# D5035-01.net
KiCad netlist of a schematic drawn in Altium Designer
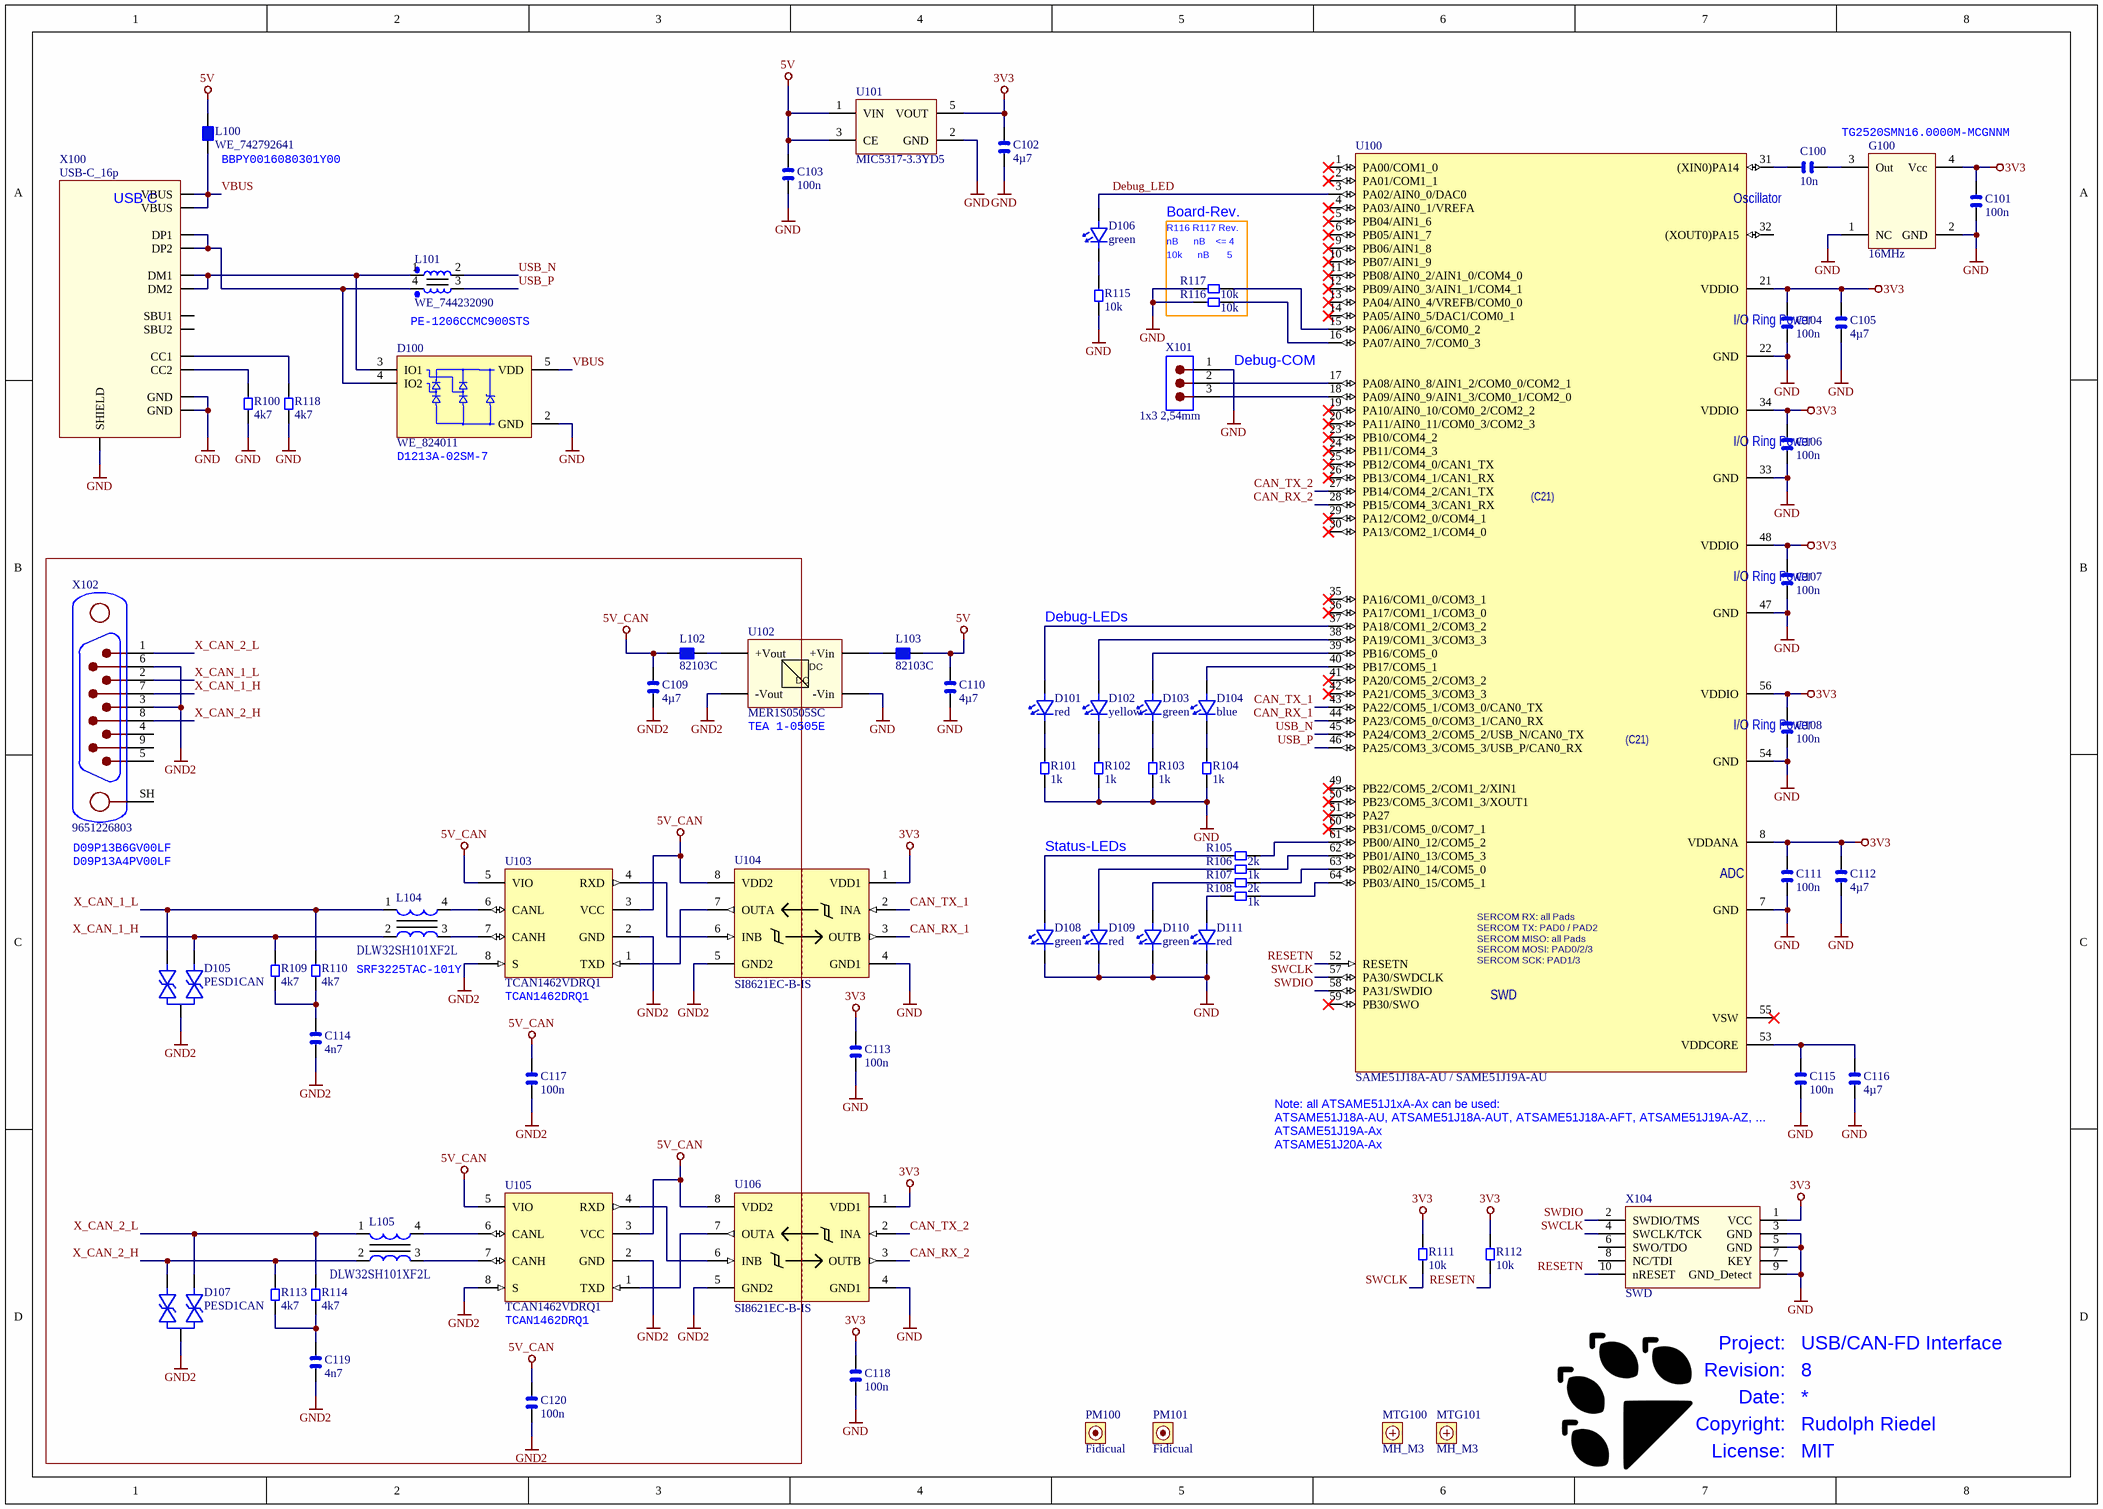
[diagram p0: D5035-01.SchDoc]

(export (version "E")
  (design (tool "Eeschema 10.0.6"))
  (components
    (comp (ref "C100")
      (value "10n")
      (footprint "CAPC1608X09L")
      (description "0603 Chip Capacitor")
      (fields (field (name "PART NUMBER") "CAPC_0603") (field (name "EDITOR") "rriedel"))
      (libsource (lib "HW-Labor_GF") (part "CAP_2_V2"))
    )
    (comp (ref "C101")
      (value "100n")
      (footprint "CAPC1608X09L")
      (description "0603 Chip Capacitor")
      (fields (field (name "PART NUMBER") "CAPC_0603") (field (name "EDITOR") "rriedel"))
      (libsource (lib "HW-Labor_GF") (part "CAP_2_V2"))
    )
    (comp (ref "C102")
      (value "4µ7")
      (footprint "CAPC2012X14L")
      (description "0805 Chip Capacitor")
      (fields (field (name "PART NUMBER") "CAPC_0805") (field (name "EDITOR") "rriedel"))
      (libsource (lib "HW-Labor_GF") (part "CAP_2_V2"))
    )
    (comp (ref "C103")
      (value "100n")
      (footprint "CAPC1608X09L")
      (description "0603 Chip Capacitor")
      (fields (field (name "PART NUMBER") "CAPC_0603") (field (name "EDITOR") "rriedel"))
      (libsource (lib "HW-Labor_GF") (part "CAP_2_V2"))
    )
    (comp (ref "C104")
      (value "100n")
      (footprint "CAPC1608X09L")
      (description "0603 Chip Capacitor")
      (fields (field (name "PART NUMBER") "CAPC_0603") (field (name "EDITOR") "rriedel"))
      (libsource (lib "HW-Labor_GF") (part "CAP_2_V2"))
    )
    (comp (ref "C105")
      (value "4µ7")
      (footprint "CAPC2012X14L")
      (description "0805 Chip Capacitor")
      (fields (field (name "PART NUMBER") "CAPC_0805") (field (name "EDITOR") "rriedel"))
      (libsource (lib "HW-Labor_GF") (part "CAP_2_V2"))
    )
    (comp (ref "C106")
      (value "100n")
      (footprint "CAPC1608X09L")
      (description "0603 Chip Capacitor")
      (fields (field (name "PART NUMBER") "CAPC_0603") (field (name "EDITOR") "rriedel"))
      (libsource (lib "HW-Labor_GF") (part "CAP_2_V2"))
    )
    (comp (ref "C107")
      (value "100n")
      (footprint "CAPC1608X09L")
      (description "0603 Chip Capacitor")
      (fields (field (name "PART NUMBER") "CAPC_0603") (field (name "EDITOR") "rriedel"))
      (libsource (lib "HW-Labor_GF") (part "CAP_2_V2"))
    )
    (comp (ref "C108")
      (value "100n")
      (footprint "CAPC1608X09L")
      (description "0603 Chip Capacitor")
      (fields (field (name "PART NUMBER") "CAPC_0603") (field (name "EDITOR") "rriedel"))
      (libsource (lib "HW-Labor_GF") (part "CAP_2_V2"))
    )
    (comp (ref "C109")
      (value "4µ7")
      (footprint "CAPC2012X14L")
      (description "0805 Chip Capacitor")
      (fields (field (name "PART NUMBER") "CAPC_0805") (field (name "EDITOR") "rriedel"))
      (libsource (lib "HW-Labor_GF") (part "CAP_2_V2"))
    )
    (comp (ref "C110")
      (value "4µ7")
      (footprint "CAPC2012X14L")
      (description "0805 Chip Capacitor")
      (fields (field (name "PART NUMBER") "CAPC_0805") (field (name "EDITOR") "rriedel"))
      (libsource (lib "HW-Labor_GF") (part "CAP_2_V2"))
    )
    (comp (ref "C111")
      (value "100n")
      (footprint "CAPC1608X09L")
      (description "0603 Chip Capacitor")
      (fields (field (name "PART NUMBER") "CAPC_0603") (field (name "EDITOR") "rriedel"))
      (libsource (lib "HW-Labor_GF") (part "CAP_2_V2"))
    )
    (comp (ref "C112")
      (value "4µ7")
      (footprint "CAPC2012X14L")
      (description "0805 Chip Capacitor")
      (fields (field (name "PART NUMBER") "CAPC_0805") (field (name "EDITOR") "rriedel"))
      (libsource (lib "HW-Labor_GF") (part "CAP_2_V2"))
    )
    (comp (ref "C113")
      (value "100n")
      (footprint "CAPC1608X09L")
      (description "0603 Chip Capacitor")
      (fields (field (name "PART NUMBER") "CAPC_0603") (field (name "EDITOR") "rriedel"))
      (libsource (lib "HW-Labor_GF") (part "CAP_2_V2"))
    )
    (comp (ref "C114")
      (value "4n7")
      (footprint "CAPC2012X14L")
      (description "0805 Chip Capacitor")
      (fields (field (name "PART NUMBER") "CAPC_0805") (field (name "EDITOR") "rriedel"))
      (libsource (lib "HW-Labor_GF") (part "CAP_2_V2"))
    )
    (comp (ref "C115")
      (value "100n")
      (footprint "CAPC1608X09L")
      (description "0603 Chip Capacitor")
      (fields (field (name "PART NUMBER") "CAPC_0603") (field (name "EDITOR") "rriedel"))
      (libsource (lib "HW-Labor_GF") (part "CAP_2_V2"))
    )
    (comp (ref "C116")
      (value "4µ7")
      (footprint "CAPC2012X14L")
      (description "0805 Chip Capacitor")
      (fields (field (name "PART NUMBER") "CAPC_0805") (field (name "EDITOR") "rriedel"))
      (libsource (lib "HW-Labor_GF") (part "CAP_2_V2"))
    )
    (comp (ref "C117")
      (value "100n")
      (footprint "CAPC1608X09L")
      (description "0603 Chip Capacitor")
      (fields (field (name "PART NUMBER") "CAPC_0603") (field (name "EDITOR") "rriedel"))
      (libsource (lib "HW-Labor_GF") (part "CAP_2_V2"))
    )
    (comp (ref "C118")
      (value "100n")
      (footprint "CAPC1608X09L")
      (description "0603 Chip Capacitor")
      (fields (field (name "PART NUMBER") "CAPC_0603") (field (name "EDITOR") "rriedel"))
      (libsource (lib "HW-Labor_GF") (part "CAP_2_V2"))
    )
    (comp (ref "C119")
      (value "4n7")
      (footprint "CAPC2012X14L")
      (description "0805 Chip Capacitor")
      (fields (field (name "PART NUMBER") "CAPC_0805") (field (name "EDITOR") "rriedel"))
      (libsource (lib "HW-Labor_GF") (part "CAP_2_V2"))
    )
    (comp (ref "C120")
      (value "100n")
      (footprint "CAPC1608X09L")
      (description "0603 Chip Capacitor")
      (fields (field (name "PART NUMBER") "CAPC_0603") (field (name "EDITOR") "rriedel"))
      (libsource (lib "HW-Labor_GF") (part "CAP_2_V2"))
    )
    (comp (ref "D100")
      (value "WE_824011")
      (footprint "SOT95P280X110-5N")
      (description "TVS Diode Array WE-TVS")
      (fields
        (field (name "MANUFACTURER") "Wuerth")
        (field (name "DISTRIBUTOR_1_PART_NUMBER") "732-4465-1-ND")
        (field (name "EDITOR") "rriedel")
      )
      (libsource (lib "HW-Labor_GF") (part "WE-824011"))
    )
    (comp (ref "D101")
      (value "red")
      (footprint "DIOC1608X06N_LED")
      (description "LED, 0603")
      (fields (field (name "PART NUMBER") "LED_0603") (field (name "EDITOR") "rriedel"))
      (libsource (lib "HW-Labor_GF") (part "LED_generic"))
    )
    (comp (ref "D102")
      (value "yellow")
      (footprint "DIOC1608X06N_LED")
      (description "LED, 0603")
      (fields (field (name "PART NUMBER") "LED_0603") (field (name "EDITOR") "rriedel"))
      (libsource (lib "HW-Labor_GF") (part "LED_generic"))
    )
    (comp (ref "D103")
      (value "green")
      (footprint "DIOC1608X06N_LED")
      (description "LED, 0603")
      (fields (field (name "PART NUMBER") "LED_0603") (field (name "EDITOR") "rriedel"))
      (libsource (lib "HW-Labor_GF") (part "LED_generic"))
    )
    (comp (ref "D104")
      (value "blue")
      (footprint "DIOC1608X06N_LED")
      (description "LED, 0603")
      (fields (field (name "PART NUMBER") "LED_0603") (field (name "EDITOR") "rriedel"))
      (libsource (lib "HW-Labor_GF") (part "LED_generic"))
    )
    (comp (ref "D105")
      (value "PESD1CAN")
      (footprint "SOT95P280X110-3N")
      (description "CAN bus ESD protection diode")
      (fields
        (field (name "MANUFACTURER") "Nexperia")
        (field (name "DISTRIBUTOR_1_PART_NUMBER") "1727-3817-1-ND")
        (field (name "EDITOR") "rriedel")
      )
      (libsource (lib "HW-Labor_GF") (part "PESD1CAN"))
    )
    (comp (ref "D106")
      (value "green")
      (footprint "DIOC1608X06N_LED")
      (description "LED, 0603")
      (fields (field (name "PART NUMBER") "LED_0603") (field (name "EDITOR") "rriedel"))
      (libsource (lib "HW-Labor_GF") (part "LED_generic"))
    )
    (comp (ref "D107")
      (value "PESD1CAN")
      (footprint "SOT95P280X110-3N")
      (description "CAN bus ESD protection diode")
      (fields
        (field (name "MANUFACTURER") "Nexperia")
        (field (name "DISTRIBUTOR_1_PART_NUMBER") "1727-3817-1-ND")
        (field (name "EDITOR") "rriedel")
      )
      (libsource (lib "HW-Labor_GF") (part "PESD1CAN"))
    )
    (comp (ref "D108")
      (value "green")
      (footprint "DIOC1608X06N_LED")
      (description "LED, 0603")
      (fields (field (name "PART NUMBER") "LED_0603") (field (name "EDITOR") "rriedel"))
      (libsource (lib "HW-Labor_GF") (part "LED_generic"))
    )
    (comp (ref "D109")
      (value "red")
      (footprint "DIOC1608X06N_LED")
      (description "LED, 0603")
      (fields (field (name "PART NUMBER") "LED_0603") (field (name "EDITOR") "rriedel"))
      (libsource (lib "HW-Labor_GF") (part "LED_generic"))
    )
    (comp (ref "D110")
      (value "green")
      (footprint "DIOC1608X06N_LED")
      (description "LED, 0603")
      (fields (field (name "PART NUMBER") "LED_0603") (field (name "EDITOR") "rriedel"))
      (libsource (lib "HW-Labor_GF") (part "LED_generic"))
    )
    (comp (ref "D111")
      (value "red")
      (footprint "DIOC1608X06N_LED")
      (description "LED, 0603")
      (fields (field (name "PART NUMBER") "LED_0603") (field (name "EDITOR") "rriedel"))
      (libsource (lib "HW-Labor_GF") (part "LED_generic"))
    )
    (comp (ref "G100")
      (value "16MHz")
      (footprint "TG2520")
      (description "16MHz Oscillator, +/- 0.5ppm")
      (fields
        (field (name "PART NUMBER") "TG2520SMN16.0000M-MCGNNM")
        (field (name "MANUFACTURER") "Epson")
        (field (name "EDITOR") "rriedel")
      )
      (libsource (lib "HW-Labor_GF") (part "TG2520"))
    )
    (comp (ref "L100")
      (value "WE_742792641")
      (footprint "INDC1608X06L")
      (description "SMT EMI suppression ferrite bead WE-CBF")
      (fields
        (field (name "MANUFACTURER") "Wuerth")
        (field (name "DISTRIBUTOR_1_PART_NUMBER") "732-1592-1-ND")
        (field (name "EDITOR") "rriedel")
      )
      (libsource (lib "HW-Labor_GF") (part "IND_2_V1"))
    )
    (comp (ref "L101")
      (value "WE_744232090")
      (footprint "WE_744232090")
      (description "SMD common mode noise suppressor WE-CNSW")
      (fields
        (field (name "MANUFACTURER") "Wuerth")
        (field (name "DISTRIBUTOR_1_PART_NUMBER") "732-1469-1-ND")
        (field (name "EDITOR") "rriedel")
      )
      (libsource (lib "HW-Labor_GF") (part "WE_744232090"))
    )
    (comp (ref "L102")
      (value "82103C")
      (footprint "Murata_8200C")
      (description "10µH, 0,5A, 400mR")
      (fields
        (field (name "MANUFACTURER") "Murata")
        (field (name "DISTRIBUTOR_1_PART_NUMBER") "811-2473-1-ND")
        (field (name "EDITOR") "rriedel")
      )
      (libsource (lib "HW-Labor_GF") (part "IND_2_V1"))
    )
    (comp (ref "L103")
      (value "82103C")
      (footprint "Murata_8200C")
      (description "10µH, 0,5A, 400mR")
      (fields
        (field (name "MANUFACTURER") "Murata")
        (field (name "DISTRIBUTOR_1_PART_NUMBER") "811-2473-1-ND")
        (field (name "EDITOR") "rriedel")
      )
      (libsource (lib "HW-Labor_GF") (part "IND_2_V1"))
    )
    (comp (ref "L104")
      (value "DLW32SH101XF2L‎")
      (footprint "ACT1210")
      (description "Common Mode Filter,  -50°C ... +150°C, AEC-Q200")
      (fields
        (field (name "PART NUMBER") "ACT1210-101-2P-TL00")
        (field (name "MANUFACTURER") "TDK")
        (field (name "EDITOR") "rriedel")
      )
      (libsource (lib "HW-Labor_GF") (part "CAN_DROSSEL"))
    )
    (comp (ref "L105")
      (value "DLW32SH101XF2L‎")
      (footprint "ACT1210")
      (description "Common Mode Filter,  -50°C ... +150°C, AEC-Q200")
      (fields
        (field (name "PART NUMBER") "ACT1210-101-2P-TL00")
        (field (name "MANUFACTURER") "TDK")
        (field (name "EDITOR") "rriedel")
      )
      (libsource (lib "HW-Labor_GF") (part "CAN_DROSSEL"))
    )
    (comp (ref "MTG100")
      (value "MH_M3")
      (footprint "HOLE_3_2MM")
      (description "Mounting-Hole for M3 screws")
      (fields (field (name "EDITOR") "rriedel"))
      (libsource (lib "HW-Labor_GF") (part "MTG_V1"))
    )
    (comp (ref "MTG101")
      (value "MH_M3")
      (footprint "HOLE_3_2MM")
      (description "Mounting-Hole for M3 screws")
      (fields (field (name "EDITOR") "rriedel"))
      (libsource (lib "HW-Labor_GF") (part "MTG_V1"))
    )
    (comp (ref "PM100")
      (value "Fidicual")
      (footprint "PM100")
      (fields (field (name "PART NUMBER") "PM100") (field (name "EDITOR") "rriedel"))
      (libsource (lib "HW-Labor_GF") (part "PM100"))
    )
    (comp (ref "PM101")
      (value "Fidicual")
      (footprint "PM100")
      (fields (field (name "PART NUMBER") "PM100") (field (name "EDITOR") "rriedel"))
      (libsource (lib "HW-Labor_GF") (part "PM100"))
    )
    (comp (ref "R100")
      (value "4k7")
      (footprint "RESC2012X06L")
      (description "0805 Chip Resistor")
      (fields (field (name "PART NUMBER") "RESC_0805") (field (name "EDITOR") "rriedel"))
      (libsource (lib "HW-Labor_GF") (part "RES_2_V2"))
    )
    (comp (ref "R101")
      (value "1k")
      (footprint "RESC1608X06L")
      (description "0603 Chip Resistor")
      (fields (field (name "PART NUMBER") "RESC_0603") (field (name "EDITOR") "rriedel"))
      (libsource (lib "HW-Labor_GF") (part "RES_2_V2"))
    )
    (comp (ref "R102")
      (value "1k")
      (footprint "RESC1608X06L")
      (description "0603 Chip Resistor")
      (fields (field (name "PART NUMBER") "RESC_0603") (field (name "EDITOR") "rriedel"))
      (libsource (lib "HW-Labor_GF") (part "RES_2_V2"))
    )
    (comp (ref "R103")
      (value "1k")
      (footprint "RESC1608X06L")
      (description "0603 Chip Resistor")
      (fields (field (name "PART NUMBER") "RESC_0603") (field (name "EDITOR") "rriedel"))
      (libsource (lib "HW-Labor_GF") (part "RES_2_V2"))
    )
    (comp (ref "R104")
      (value "1k")
      (footprint "RESC1608X06L")
      (description "0603 Chip Resistor")
      (fields (field (name "PART NUMBER") "RESC_0603") (field (name "EDITOR") "rriedel"))
      (libsource (lib "HW-Labor_GF") (part "RES_2_V2"))
    )
    (comp (ref "R105")
      (value "2k")
      (footprint "RESC1608X06L")
      (description "0603 Chip Resistor")
      (fields (field (name "PART NUMBER") "RESC_0603") (field (name "EDITOR") "rriedel"))
      (libsource (lib "HW-Labor_GF") (part "RES_2_V2"))
    )
    (comp (ref "R106")
      (value "1k")
      (footprint "RESC1608X06L")
      (description "0603 Chip Resistor")
      (fields (field (name "PART NUMBER") "RESC_0603") (field (name "EDITOR") "rriedel"))
      (libsource (lib "HW-Labor_GF") (part "RES_2_V2"))
    )
    (comp (ref "R107")
      (value "2k")
      (footprint "RESC1608X06L")
      (description "0603 Chip Resistor")
      (fields (field (name "PART NUMBER") "RESC_0603") (field (name "EDITOR") "rriedel"))
      (libsource (lib "HW-Labor_GF") (part "RES_2_V2"))
    )
    (comp (ref "R108")
      (value "1k")
      (footprint "RESC1608X06L")
      (description "0603 Chip Resistor")
      (fields (field (name "PART NUMBER") "RESC_0603") (field (name "EDITOR") "rriedel"))
      (libsource (lib "HW-Labor_GF") (part "RES_2_V2"))
    )
    (comp (ref "R109")
      (value "4k7")
      (footprint "RESC2012X06L")
      (description "0805 Chip Resistor")
      (fields (field (name "PART NUMBER") "RESC_0805") (field (name "EDITOR") "rriedel"))
      (libsource (lib "HW-Labor_GF") (part "RES_2_V2"))
    )
    (comp (ref "R110")
      (value "4k7")
      (footprint "RESC2012X06L")
      (description "0805 Chip Resistor")
      (fields (field (name "PART NUMBER") "RESC_0805") (field (name "EDITOR") "rriedel"))
      (libsource (lib "HW-Labor_GF") (part "RES_2_V2"))
    )
    (comp (ref "R111")
      (value "10k")
      (footprint "RESC1608X06L")
      (description "0603 Chip Resistor")
      (fields (field (name "PART NUMBER") "RESC_0603") (field (name "EDITOR") "rriedel"))
      (libsource (lib "HW-Labor_GF") (part "RES_2_V2"))
    )
    (comp (ref "R112")
      (value "10k")
      (footprint "RESC1608X06L")
      (description "0603 Chip Resistor")
      (fields (field (name "PART NUMBER") "RESC_0603") (field (name "EDITOR") "rriedel"))
      (libsource (lib "HW-Labor_GF") (part "RES_2_V2"))
    )
    (comp (ref "R113")
      (value "4k7")
      (footprint "RESC2012X06L")
      (description "0805 Chip Resistor")
      (fields (field (name "PART NUMBER") "RESC_0805") (field (name "EDITOR") "rriedel"))
      (libsource (lib "HW-Labor_GF") (part "RES_2_V2"))
    )
    (comp (ref "R114")
      (value "4k7")
      (footprint "RESC2012X06L")
      (description "0805 Chip Resistor")
      (fields (field (name "PART NUMBER") "RESC_0805") (field (name "EDITOR") "rriedel"))
      (libsource (lib "HW-Labor_GF") (part "RES_2_V2"))
    )
    (comp (ref "R115")
      (value "10k")
      (footprint "RESC1608X06L")
      (description "0603 Chip Resistor")
      (fields (field (name "PART NUMBER") "RESC_0603") (field (name "EDITOR") "rriedel"))
      (libsource (lib "HW-Labor_GF") (part "RES_2_V2"))
    )
    (comp (ref "R116")
      (value "10k")
      (footprint "RESC1608X06L")
      (description "0603 Chip Resistor")
      (fields (field (name "PART NUMBER") "RESC_0603") (field (name "EDITOR") "rriedel"))
      (libsource (lib "HW-Labor_GF") (part "RES_2_V2"))
    )
    (comp (ref "R117")
      (value "10k")
      (footprint "RESC1608X06L")
      (description "0603 Chip Resistor")
      (fields (field (name "PART NUMBER") "RESC_0603") (field (name "EDITOR") "rriedel"))
      (libsource (lib "HW-Labor_GF") (part "RES_2_V2"))
    )
    (comp (ref "R118")
      (value "4k7")
      (footprint "RESC2012X06L")
      (description "0805 Chip Resistor")
      (fields (field (name "PART NUMBER") "RESC_0805") (field (name "EDITOR") "rriedel"))
      (libsource (lib "HW-Labor_GF") (part "RES_2_V2"))
    )
    (comp (ref "U100")
      (value "SAME51J18A-AU / SAME51J19A-AU")
      (footprint "TSQFP50P1200X1200X120-64N")
      (description "32-bit Microcontroller, 120MHz Cortex M4-F, 512k FLASH,  2x CAN-FD, -40…85°C")
      (fields
        (field (name "PART NUMBER") "SAME51J19A-AU")
        (field (name "MANUFACTURER") "Microchip")
        (field (name "EDITOR") "rriedel")
      )
      (libsource (lib "HW-Labor_GF") (part "SAME5xJxxA-AUx"))
    )
    (comp (ref "U101")
      (value "MIC5317-3.3YD5")
      (footprint "SOT95P280X110-5N")
      (description "100 mA LDO,  Vout= 3,3V, -40°C..125°C")
      (fields
        (field (name "PART NUMBER") "MIC5233-3.3")
        (field (name "MANUFACTURER") "Microchip")
        (field (name "EDITOR") "rriedel")
      )
      (libsource (lib "HW-Labor_GF") (part "LDO_SOT23-5"))
    )
    (comp (ref "U102")
      (value "MER1S0505SC")
      (footprint "MER1SxxxxC")
      (description "Isolated 1W Single Output DC-DC Converters 5V/5V 200mA")
      (fields
        (field (name "MANUFACTURER") "Murata")
        (field (name "DISTRIBUTOR_1_PART_NUMBER") "811-2124-5-ND‎")
        (field (name "EDITOR") "rriedel")
      )
      (libsource (lib "HW-Labor_GF") (part "MER1SxxxxC"))
    )
    (comp (ref "U103")
      (value "TCAN1462VDRQ1")
      (footprint "SOIC127P600X175-8N")
      (description "CAN-FD SIC transceiver 8MBit, VIO Pin")
      (fields
        (field (name "MANUFACTURER") "TI")
        (field (name "DISTRIBUTOR_1_PART_NUMBER") "595-TCAN1462VDRQ1")
        (field (name "EDITOR") "rriedel")
      )
      (libsource (lib "HW-Labor_GF") (part "TJA1051T_3"))
    )
    (comp (ref "U104")
      (value "SI8621EC-B-IS")
      (footprint "SOIC127P600X175-8N")
      (description "Dual channel digital isolator, 150Mbit, 3,75kV")
      (fields
        (field (name "MANUFACTURER") "Silicon Labs")
        (field (name "DISTRIBUTOR_1_PART_NUMBER") "336-4776-1-ND")
        (field (name "EDITOR") "rriedel")
      )
      (libsource (lib "HW-Labor_GF") (part "SI8621"))
    )
    (comp (ref "U105")
      (value "TCAN1462VDRQ1")
      (footprint "SOIC127P600X175-8N")
      (description "CAN-FD SIC transceiver 8MBit, VIO Pin")
      (fields
        (field (name "MANUFACTURER") "TI")
        (field (name "DISTRIBUTOR_1_PART_NUMBER") "595-TCAN1462VDRQ1")
        (field (name "EDITOR") "rriedel")
      )
      (libsource (lib "HW-Labor_GF") (part "TJA1051T_3"))
    )
    (comp (ref "U106")
      (value "SI8621EC-B-IS")
      (footprint "SOIC127P600X175-8N")
      (description "Dual channel digital isolator, 150Mbit, 3,75kV")
      (fields
        (field (name "MANUFACTURER") "Silicon Labs")
        (field (name "DISTRIBUTOR_1_PART_NUMBER") "336-4776-1-ND")
        (field (name "EDITOR") "rriedel")
      )
      (libsource (lib "HW-Labor_GF") (part "SI8621"))
    )
    (comp (ref "X100")
      (value "USB-C_16p")
      (footprint "USBC_16P")
      (description "SMD USB-C 16p")
      (fields (field (name "DISTRIBUTOR_1_PART_NUMBER") "C2765186") (field (name "EDITOR") "rriedel"))
      (libsource (lib "HW-Labor_GF") (part "USB-C"))
    )
    (comp (ref "X101")
      (value "1x3 2,54mm")
      (footprint "PINH_1x03_2_54mm")
      (description "Pin-Header 2,54 mm 3pins")
      (fields (field (name "PART NUMBER") "PINH_1x3_2_54") (field (name "EDITOR") "rriedel"))
      (libsource (lib "HW-Labor_GF") (part "CONM_1x3_V2"))
    )
    (comp (ref "X102")
      (value "9651226803")
      (footprint "09651226803")
      (description "D-Sub, 9 pin, male, right angle")
      (fields
        (field (name "PART NUMBER") "09651226803")
        (field (name "MANUFACTURER") "Harting")
        (field (name "EDITOR") "rriedel")
      )
      (libsource (lib "HW-Labor_GF") (part "D_Sub_9_Male"))
    )
    (comp (ref "X104")
      (value "SWD")
      (footprint "FTSH-105-01-L-DV-K")
      (description "ARM Debug-Header 2x5 1,27 mm")
      (fields (field (name "EDITOR") "rriedel"))
      (libsource (lib "HW-Labor_GF") (part "SWD"))
    )
  )
  (nets
    (net (code "1") (name "/CAN_RX_1") (class "Default")
      (node (ref "U100") (pin "44") (pinfunction "PA23/COM5_0/COM3_1/CAN0_RX_44") (pintype "bidirectional"))
      (node (ref "U104") (pin "3") (pinfunction "OUTB_3") (pintype "output"))
    )
    (net (code "2") (name "/CAN_RX_2") (class "Default")
      (node (ref "U100") (pin "28") (pinfunction "PB15/COM4_3/CAN1_RX_28") (pintype "bidirectional"))
      (node (ref "U106") (pin "3") (pinfunction "OUTB_3") (pintype "output"))
    )
    (net (code "3") (name "/CAN_TX_1") (class "Default")
      (node (ref "U100") (pin "43") (pinfunction "PA22/COM5_1/COM3_0/CAN0_TX_43") (pintype "bidirectional"))
      (node (ref "U104") (pin "2") (pinfunction "INA_2") (pintype "input"))
    )
    (net (code "4") (name "/CAN_TX_2") (class "Default")
      (node (ref "U100") (pin "27") (pinfunction "PB14/COM4_2/CAN1_TX_27") (pintype "bidirectional"))
      (node (ref "U106") (pin "2") (pinfunction "INA_2") (pintype "input"))
    )
    (net (code "5") (name "/Debug_LED") (class "Default")
      (node (ref "D106") (pin "2") (pinfunction "2_2") (pintype "passive"))
      (node (ref "U100") (pin "3") (pinfunction "PA02/AIN0_0/DAC0_3") (pintype "bidirectional"))
    )
    (net (code "6") (name "/RESETN") (class "Default")
      (node (ref "R112") (pin "1") (pinfunction "1_1") (pintype "passive"))
      (node (ref "U100") (pin "52") (pinfunction "RESETN_52") (pintype "input"))
      (node (ref "X104") (pin "10") (pinfunction "nRESET_10") (pintype "passive"))
    )
    (net (code "7") (name "/SWCLK") (class "Default")
      (node (ref "R111") (pin "1") (pinfunction "1_1") (pintype "passive"))
      (node (ref "U100") (pin "57") (pinfunction "PA30/SWDCLK_57") (pintype "bidirectional"))
      (node (ref "X104") (pin "4") (pinfunction "SWCLK/TCK_4") (pintype "passive"))
    )
    (net (code "8") (name "/SWDIO") (class "Default")
      (node (ref "U100") (pin "58") (pinfunction "PA31/SWDIO_58") (pintype "bidirectional"))
      (node (ref "X104") (pin "2") (pinfunction "SWDIO/TMS_2") (pintype "passive"))
    )
    (net (code "9") (name "/USB_N") (class "Default")
      (node (ref "L101") (pin "2") (pinfunction "2_2") (pintype "passive"))
      (node (ref "U100") (pin "45") (pinfunction "PA24/COM3_2/COM5_2/USB_N/CAN0_TX_45") (pintype "bidirectional"))
    )
    (net (code "10") (name "/USB_P") (class "Default")
      (node (ref "L101") (pin "3") (pinfunction "3_3") (pintype "passive"))
      (node (ref "U100") (pin "46") (pinfunction "PA25/COM3_3/COM5_3/USB_P/CAN0_RX_46") (pintype "bidirectional"))
    )
    (net (code "11") (name "/VBUS") (class "Default")
      (node (ref "D100") (pin "5") (pinfunction "VDD_5") (pintype "passive"))
      (node (ref "L100") (pin "1") (pinfunction "1_1") (pintype "passive"))
      (node (ref "X100") (pin "A4-B9") (pinfunction "VBUS_A4-B9") (pintype "power_in"))
      (node (ref "X100") (pin "B4-A9") (pinfunction "VBUS_B4-A9") (pintype "power_in"))
    )
    (net (code "12") (name "/X_CAN_1_H") (class "Default")
      (node (ref "D105") (pin "2") (pinfunction "2_2") (pintype "passive"))
      (node (ref "L104") (pin "2") (pintype "passive"))
      (node (ref "R109") (pin "2") (pinfunction "2_2") (pintype "passive"))
      (node (ref "X102") (pin "7") (pinfunction "7_7") (pintype "passive"))
    )
    (net (code "13") (name "/X_CAN_1_L") (class "Default")
      (node (ref "D105") (pin "1") (pinfunction "1_1") (pintype "passive"))
      (node (ref "L104") (pin "1") (pintype "passive"))
      (node (ref "R110") (pin "2") (pinfunction "2_2") (pintype "passive"))
      (node (ref "X102") (pin "2") (pinfunction "2_2") (pintype "passive"))
    )
    (net (code "14") (name "/X_CAN_2_H") (class "Default")
      (node (ref "D107") (pin "1") (pinfunction "1_1") (pintype "passive"))
      (node (ref "L105") (pin "2") (pintype "passive"))
      (node (ref "R113") (pin "2") (pinfunction "2_2") (pintype "passive"))
      (node (ref "X102") (pin "8") (pinfunction "8_8") (pintype "passive"))
    )
    (net (code "15") (name "/X_CAN_2_L") (class "Default")
      (node (ref "D107") (pin "2") (pinfunction "2_2") (pintype "passive"))
      (node (ref "L105") (pin "1") (pintype "passive"))
      (node (ref "R114") (pin "2") (pinfunction "2_2") (pintype "passive"))
      (node (ref "X102") (pin "1") (pinfunction "1_1") (pintype "passive"))
    )
    (net (code "16") (name "3V3") (class "Default")
      (node (ref "C101") (pin "2") (pinfunction "2_2") (pintype "passive"))
      (node (ref "C102") (pin "2") (pinfunction "2_2") (pintype "passive"))
      (node (ref "C104") (pin "2") (pinfunction "2_2") (pintype "passive"))
      (node (ref "C105") (pin "2") (pinfunction "2_2") (pintype "passive"))
      (node (ref "C106") (pin "2") (pinfunction "2_2") (pintype "passive"))
      (node (ref "C107") (pin "2") (pinfunction "2_2") (pintype "passive"))
      (node (ref "C108") (pin "2") (pinfunction "2_2") (pintype "passive"))
      (node (ref "C111") (pin "2") (pinfunction "2_2") (pintype "passive"))
      (node (ref "C112") (pin "2") (pinfunction "2_2") (pintype "passive"))
      (node (ref "C113") (pin "2") (pinfunction "2_2") (pintype "passive"))
      (node (ref "C118") (pin "2") (pinfunction "2_2") (pintype "passive"))
      (node (ref "G100") (pin "4") (pinfunction "Vcc_4") (pintype "passive"))
      (node (ref "R111") (pin "2") (pinfunction "2_2") (pintype "passive"))
      (node (ref "R112") (pin "2") (pinfunction "2_2") (pintype "passive"))
      (node (ref "U100") (pin "21") (pinfunction "VDDIO_21") (pintype "power_in"))
      (node (ref "U100") (pin "34") (pinfunction "VDDIO_34") (pintype "power_in"))
      (node (ref "U100") (pin "48") (pinfunction "VDDIO_48") (pintype "power_in"))
      (node (ref "U100") (pin "56") (pinfunction "VDDIO_56") (pintype "power_in"))
      (node (ref "U100") (pin "8") (pinfunction "VDDANA_8") (pintype "power_in"))
      (node (ref "U101") (pin "5") (pinfunction "VOUT_5") (pintype "passive"))
      (node (ref "U104") (pin "1") (pinfunction "VDD1_1") (pintype "power_in"))
      (node (ref "U106") (pin "1") (pinfunction "VDD1_1") (pintype "power_in"))
      (node (ref "X104") (pin "1") (pinfunction "VCC_1") (pintype "power_in"))
    )
    (net (code "17") (name "5V") (class "Default")
      (node (ref "C103") (pin "2") (pinfunction "2_2") (pintype "passive"))
      (node (ref "C110") (pin "2") (pinfunction "2_2") (pintype "passive"))
      (node (ref "L100") (pin "2") (pinfunction "2_2") (pintype "passive"))
      (node (ref "L103") (pin "1") (pinfunction "1_1") (pintype "passive"))
      (node (ref "U101") (pin "1") (pinfunction "VIN_1") (pintype "passive"))
      (node (ref "U101") (pin "3") (pinfunction "CE_3") (pintype "passive"))
    )
    (net (code "18") (name "5V_CAN") (class "Default")
      (node (ref "C109") (pin "2") (pinfunction "2_2") (pintype "passive"))
      (node (ref "C117") (pin "2") (pinfunction "2_2") (pintype "passive"))
      (node (ref "C120") (pin "2") (pinfunction "2_2") (pintype "passive"))
      (node (ref "L102") (pin "2") (pinfunction "2_2") (pintype "passive"))
      (node (ref "U103") (pin "3") (pinfunction "VCC_3") (pintype "power_in"))
      (node (ref "U103") (pin "5") (pinfunction "VIO_5") (pintype "power_in"))
      (node (ref "U104") (pin "8") (pinfunction "VDD2_8") (pintype "power_in"))
      (node (ref "U105") (pin "3") (pinfunction "VCC_3") (pintype "power_in"))
      (node (ref "U105") (pin "5") (pinfunction "VIO_5") (pintype "power_in"))
      (node (ref "U106") (pin "8") (pinfunction "VDD2_8") (pintype "power_in"))
    )
    (net (code "19") (name "GND") (class "Default")
      (node (ref "C101") (pin "1") (pinfunction "1_1") (pintype "passive"))
      (node (ref "C102") (pin "1") (pinfunction "1_1") (pintype "passive"))
      (node (ref "C103") (pin "1") (pinfunction "1_1") (pintype "passive"))
      (node (ref "C104") (pin "1") (pinfunction "1_1") (pintype "passive"))
      (node (ref "C105") (pin "1") (pinfunction "1_1") (pintype "passive"))
      (node (ref "C106") (pin "1") (pinfunction "1_1") (pintype "passive"))
      (node (ref "C107") (pin "1") (pinfunction "1_1") (pintype "passive"))
      (node (ref "C108") (pin "1") (pinfunction "1_1") (pintype "passive"))
      (node (ref "C110") (pin "1") (pinfunction "1_1") (pintype "passive"))
      (node (ref "C111") (pin "1") (pinfunction "1_1") (pintype "passive"))
      (node (ref "C112") (pin "1") (pinfunction "1_1") (pintype "passive"))
      (node (ref "C113") (pin "1") (pinfunction "1_1") (pintype "passive"))
      (node (ref "C115") (pin "1") (pinfunction "1_1") (pintype "passive"))
      (node (ref "C116") (pin "1") (pinfunction "1_1") (pintype "passive"))
      (node (ref "C118") (pin "1") (pinfunction "1_1") (pintype "passive"))
      (node (ref "D100") (pin "2") (pinfunction "GND_2") (pintype "passive"))
      (node (ref "D108") (pin "1") (pinfunction "1_1") (pintype "passive"))
      (node (ref "D109") (pin "1") (pinfunction "1_1") (pintype "passive"))
      (node (ref "D110") (pin "1") (pinfunction "1_1") (pintype "passive"))
      (node (ref "D111") (pin "1") (pinfunction "1_1") (pintype "passive"))
      (node (ref "G100") (pin "1") (pinfunction "NC_1") (pintype "passive"))
      (node (ref "G100") (pin "2") (pinfunction "GND_2") (pintype "power_in"))
      (node (ref "R100") (pin "1") (pinfunction "1_1") (pintype "passive"))
      (node (ref "R101") (pin "1") (pinfunction "1_1") (pintype "passive"))
      (node (ref "R102") (pin "1") (pinfunction "1_1") (pintype "passive"))
      (node (ref "R103") (pin "1") (pinfunction "1_1") (pintype "passive"))
      (node (ref "R104") (pin "1") (pinfunction "1_1") (pintype "passive"))
      (node (ref "R115") (pin "1") (pinfunction "1_1") (pintype "passive"))
      (node (ref "R116") (pin "2") (pinfunction "2_2") (pintype "passive"))
      (node (ref "R117") (pin "2") (pinfunction "2_2") (pintype "passive"))
      (node (ref "R118") (pin "1") (pinfunction "1_1") (pintype "passive"))
      (node (ref "U100") (pin "22") (pinfunction "GND_22") (pintype "power_in"))
      (node (ref "U100") (pin "33") (pinfunction "GND_33") (pintype "power_in"))
      (node (ref "U100") (pin "47") (pinfunction "GND_47") (pintype "power_in"))
      (node (ref "U100") (pin "54") (pinfunction "GND_54") (pintype "power_in"))
      (node (ref "U100") (pin "7") (pinfunction "GND_7") (pintype "power_in"))
      (node (ref "U101") (pin "2") (pinfunction "GND_2") (pintype "passive"))
      (node (ref "U102") (pin "2") (pinfunction "-Vin_2") (pintype "power_in"))
      (node (ref "U104") (pin "4") (pinfunction "GND1_4") (pintype "power_in"))
      (node (ref "U106") (pin "4") (pinfunction "GND1_4") (pintype "power_in"))
      (node (ref "X100") (pin "A1-B12") (pinfunction "GND_A1-B12") (pintype "power_in"))
      (node (ref "X100") (pin "B1-A12") (pinfunction "GND_B1-A12") (pintype "power_in"))
      (node (ref "X100") (pin "SHIELD") (pinfunction "SHIELD_SHIELD") (pintype "passive"))
      (node (ref "X101") (pin "1") (pinfunction "1_1") (pintype "passive"))
      (node (ref "X104") (pin "3") (pinfunction "GND_3") (pintype "power_in"))
      (node (ref "X104") (pin "5") (pinfunction "GND_5") (pintype "power_in"))
      (node (ref "X104") (pin "9") (pinfunction "GND_Detect_9") (pintype "power_in"))
    )
    (net (code "20") (name "GND2") (class "Default")
      (node (ref "C109") (pin "1") (pinfunction "1_1") (pintype "passive"))
      (node (ref "C114") (pin "1") (pinfunction "1_1") (pintype "passive"))
      (node (ref "C117") (pin "1") (pinfunction "1_1") (pintype "passive"))
      (node (ref "C119") (pin "1") (pinfunction "1_1") (pintype "passive"))
      (node (ref "C120") (pin "1") (pinfunction "1_1") (pintype "passive"))
      (node (ref "D105") (pin "3") (pinfunction "3_3") (pintype "passive"))
      (node (ref "D107") (pin "3") (pinfunction "3_3") (pintype "passive"))
      (node (ref "U102") (pin "4") (pinfunction "-Vout_4") (pintype "power_in"))
      (node (ref "U103") (pin "2") (pinfunction "GND_2") (pintype "power_in"))
      (node (ref "U103") (pin "8") (pinfunction "S_8") (pintype "input"))
      (node (ref "U104") (pin "5") (pinfunction "GND2_5") (pintype "power_in"))
      (node (ref "U105") (pin "2") (pinfunction "GND_2") (pintype "power_in"))
      (node (ref "U105") (pin "8") (pinfunction "S_8") (pintype "input"))
      (node (ref "U106") (pin "5") (pinfunction "GND2_5") (pintype "power_in"))
      (node (ref "X102") (pin "3") (pinfunction "3_3") (pintype "passive"))
      (node (ref "X102") (pin "6") (pinfunction "6_6") (pintype "passive"))
    )
    (net (code "21") (name "Net-(C114-Pad2)") (class "Default")
      (node (ref "C114") (pin "2") (pinfunction "2_2") (pintype "passive"))
      (node (ref "R109") (pin "1") (pinfunction "1_1") (pintype "passive"))
      (node (ref "R110") (pin "1") (pinfunction "1_1") (pintype "passive"))
    )
    (net (code "22") (name "Net-(C119-Pad2)") (class "Default")
      (node (ref "C119") (pin "2") (pinfunction "2_2") (pintype "passive"))
      (node (ref "R113") (pin "1") (pinfunction "1_1") (pintype "passive"))
      (node (ref "R114") (pin "1") (pinfunction "1_1") (pintype "passive"))
    )
    (net (code "23") (name "Net-(D100-IO1)") (class "Default")
      (node (ref "D100") (pin "3") (pinfunction "IO1_3") (pintype "passive"))
      (node (ref "L101") (pin "1") (pinfunction "1_1") (pintype "passive"))
      (node (ref "X100") (pin "A7") (pinfunction "DM1_A7") (pintype "passive"))
      (node (ref "X100") (pin "B7") (pinfunction "DM2_B7") (pintype "passive"))
    )
    (net (code "24") (name "Net-(D100-IO2)") (class "Default")
      (node (ref "D100") (pin "4") (pinfunction "IO2_4") (pintype "passive"))
      (node (ref "L101") (pin "4") (pinfunction "4_4") (pintype "passive"))
      (node (ref "X100") (pin "A6") (pinfunction "DP1_A6") (pintype "passive"))
      (node (ref "X100") (pin "B6") (pinfunction "DP2_B6") (pintype "passive"))
    )
    (net (code "25") (name "Net-(D101-Pad1)") (class "Default")
      (node (ref "D101") (pin "1") (pinfunction "1_1") (pintype "passive"))
      (node (ref "R101") (pin "2") (pinfunction "2_2") (pintype "passive"))
    )
    (net (code "26") (name "Net-(D102-Pad1)") (class "Default")
      (node (ref "D102") (pin "1") (pinfunction "1_1") (pintype "passive"))
      (node (ref "R102") (pin "2") (pinfunction "2_2") (pintype "passive"))
    )
    (net (code "27") (name "Net-(D103-Pad1)") (class "Default")
      (node (ref "D103") (pin "1") (pinfunction "1_1") (pintype "passive"))
      (node (ref "R103") (pin "2") (pinfunction "2_2") (pintype "passive"))
    )
    (net (code "28") (name "Net-(D104-Pad1)") (class "Default")
      (node (ref "D104") (pin "1") (pinfunction "1_1") (pintype "passive"))
      (node (ref "R104") (pin "2") (pinfunction "2_2") (pintype "passive"))
    )
    (net (code "29") (name "Net-(D106-Pad1)") (class "Default")
      (node (ref "D106") (pin "1") (pinfunction "1_1") (pintype "passive"))
      (node (ref "R115") (pin "2") (pinfunction "2_2") (pintype "passive"))
    )
    (net (code "30") (name "Net-(D108-Pad2)") (class "Default")
      (node (ref "D108") (pin "2") (pinfunction "2_2") (pintype "passive"))
      (node (ref "R105") (pin "1") (pinfunction "1_1") (pintype "passive"))
    )
    (net (code "31") (name "Net-(D109-Pad2)") (class "Default")
      (node (ref "D109") (pin "2") (pinfunction "2_2") (pintype "passive"))
      (node (ref "R106") (pin "1") (pinfunction "1_1") (pintype "passive"))
    )
    (net (code "32") (name "Net-(D110-Pad2)") (class "Default")
      (node (ref "D110") (pin "2") (pinfunction "2_2") (pintype "passive"))
      (node (ref "R107") (pin "1") (pinfunction "1_1") (pintype "passive"))
    )
    (net (code "33") (name "Net-(D111-Pad2)") (class "Default")
      (node (ref "D111") (pin "2") (pinfunction "2_2") (pintype "passive"))
      (node (ref "R108") (pin "1") (pinfunction "1_1") (pintype "passive"))
    )
    (net (code "34") (name "Net-(G100-Out)") (class "Default")
      (node (ref "C100") (pin "2") (pinfunction "2_2") (pintype "passive"))
      (node (ref "G100") (pin "3") (pinfunction "Out_3") (pintype "passive"))
    )
    (net (code "35") (name "Net-(U100-(XIN0)PA14)") (class "Default")
      (node (ref "C100") (pin "1") (pinfunction "1_1") (pintype "passive"))
      (node (ref "U100") (pin "31") (pinfunction "(XIN0)PA14_31") (pintype "bidirectional"))
    )
    (net (code "36") (name "Net-(U100-PA06{slash}AIN0_6{slash}COM0_2)") (class "Default")
      (node (ref "R117") (pin "1") (pinfunction "1_1") (pintype "passive"))
      (node (ref "U100") (pin "15") (pinfunction "PA06/AIN0_6/COM0_2_15") (pintype "bidirectional"))
    )
    (net (code "37") (name "Net-(U100-PA07{slash}AIN0_7{slash}COM0_3)") (class "Default")
      (node (ref "R116") (pin "1") (pinfunction "1_1") (pintype "passive"))
      (node (ref "U100") (pin "16") (pinfunction "PA07/AIN0_7/COM0_3_16") (pintype "bidirectional"))
    )
    (net (code "38") (name "Net-(U100-PA08{slash}AIN0_8{slash}AIN1_2{slash}COM0_0{slash}COM2_1)") (class "Default")
      (node (ref "U100") (pin "17") (pinfunction "PA08/AIN0_8/AIN1_2/COM0_0/COM2_1_17") (pintype "bidirectional"))
      (node (ref "X101") (pin "2") (pinfunction "2_2") (pintype "passive"))
    )
    (net (code "39") (name "Net-(U100-PA09{slash}AIN0_9{slash}AIN1_3{slash}COM0_1{slash}COM2_0)") (class "Default")
      (node (ref "U100") (pin "18") (pinfunction "PA09/AIN0_9/AIN1_3/COM0_1/COM2_0_18") (pintype "bidirectional"))
      (node (ref "X101") (pin "3") (pinfunction "3_3") (pintype "passive"))
    )
    (net (code "40") (name "Net-(U100-PA18{slash}COM1_2{slash}COM3_2)") (class "Default")
      (node (ref "D101") (pin "2") (pinfunction "2_2") (pintype "passive"))
      (node (ref "U100") (pin "37") (pinfunction "PA18/COM1_2/COM3_2_37") (pintype "bidirectional"))
    )
    (net (code "41") (name "Net-(U100-PA19{slash}COM1_3{slash}COM3_3)") (class "Default")
      (node (ref "D102") (pin "2") (pinfunction "2_2") (pintype "passive"))
      (node (ref "U100") (pin "38") (pinfunction "PA19/COM1_3/COM3_3_38") (pintype "bidirectional"))
    )
    (net (code "42") (name "Net-(U100-PB00{slash}AIN0_12{slash}COM5_2)") (class "Default")
      (node (ref "R105") (pin "2") (pinfunction "2_2") (pintype "passive"))
      (node (ref "U100") (pin "61") (pinfunction "PB00/AIN0_12/COM5_2_61") (pintype "bidirectional"))
    )
    (net (code "43") (name "Net-(U100-PB01{slash}AIN0_13{slash}COM5_3)") (class "Default")
      (node (ref "R106") (pin "2") (pinfunction "2_2") (pintype "passive"))
      (node (ref "U100") (pin "62") (pinfunction "PB01/AIN0_13/COM5_3_62") (pintype "bidirectional"))
    )
    (net (code "44") (name "Net-(U100-PB02{slash}AIN0_14{slash}COM5_0)") (class "Default")
      (node (ref "R107") (pin "2") (pinfunction "2_2") (pintype "passive"))
      (node (ref "U100") (pin "63") (pinfunction "PB02/AIN0_14/COM5_0_63") (pintype "bidirectional"))
    )
    (net (code "45") (name "Net-(U100-PB03{slash}AIN0_15{slash}COM5_1)") (class "Default")
      (node (ref "R108") (pin "2") (pinfunction "2_2") (pintype "passive"))
      (node (ref "U100") (pin "64") (pinfunction "PB03/AIN0_15/COM5_1_64") (pintype "bidirectional"))
    )
    (net (code "46") (name "Net-(U100-PB16{slash}COM5_0)") (class "Default")
      (node (ref "D103") (pin "2") (pinfunction "2_2") (pintype "passive"))
      (node (ref "U100") (pin "39") (pinfunction "PB16/COM5_0_39") (pintype "bidirectional"))
    )
    (net (code "47") (name "Net-(U100-PB17{slash}COM5_1)") (class "Default")
      (node (ref "D104") (pin "2") (pinfunction "2_2") (pintype "passive"))
      (node (ref "U100") (pin "40") (pinfunction "PB17/COM5_1_40") (pintype "bidirectional"))
    )
    (net (code "48") (name "Net-(U100-VDDCORE)") (class "Default")
      (node (ref "C115") (pin "2") (pinfunction "2_2") (pintype "passive"))
      (node (ref "C116") (pin "2") (pinfunction "2_2") (pintype "passive"))
      (node (ref "U100") (pin "53") (pinfunction "VDDCORE_53") (pintype "passive"))
    )
    (net (code "49") (name "Net-(U102-+Vin)") (class "Default")
      (node (ref "L103") (pin "2") (pinfunction "2_2") (pintype "passive"))
      (node (ref "U102") (pin "1") (pinfunction "+Vin_1") (pintype "power_in"))
    )
    (net (code "50") (name "Net-(U102-+Vout)") (class "Default")
      (node (ref "L102") (pin "1") (pinfunction "1_1") (pintype "passive"))
      (node (ref "U102") (pin "6") (pinfunction "+Vout_6") (pintype "power_in"))
    )
    (net (code "51") (name "Net-(U103-CANH)") (class "Default")
      (node (ref "L104") (pin "3") (pintype "passive"))
      (node (ref "U103") (pin "7") (pinfunction "CANH_7") (pintype "bidirectional"))
    )
    (net (code "52") (name "Net-(U103-CANL)") (class "Default")
      (node (ref "L104") (pin "4") (pintype "passive"))
      (node (ref "U103") (pin "6") (pinfunction "CANL_6") (pintype "bidirectional"))
    )
    (net (code "53") (name "Net-(U103-RXD)") (class "Default")
      (node (ref "U103") (pin "4") (pinfunction "RXD_4") (pintype "output"))
      (node (ref "U104") (pin "6") (pinfunction "INB_6") (pintype "input"))
    )
    (net (code "54") (name "Net-(U103-TXD)") (class "Default")
      (node (ref "U103") (pin "1") (pinfunction "TXD_1") (pintype "input"))
      (node (ref "U104") (pin "7") (pinfunction "OUTA_7") (pintype "output"))
    )
    (net (code "55") (name "Net-(U105-CANH)") (class "Default")
      (node (ref "L105") (pin "3") (pintype "passive"))
      (node (ref "U105") (pin "7") (pinfunction "CANH_7") (pintype "bidirectional"))
    )
    (net (code "56") (name "Net-(U105-CANL)") (class "Default")
      (node (ref "L105") (pin "4") (pintype "passive"))
      (node (ref "U105") (pin "6") (pinfunction "CANL_6") (pintype "bidirectional"))
    )
    (net (code "57") (name "Net-(U105-RXD)") (class "Default")
      (node (ref "U105") (pin "4") (pinfunction "RXD_4") (pintype "output"))
      (node (ref "U106") (pin "6") (pinfunction "INB_6") (pintype "input"))
    )
    (net (code "58") (name "Net-(U105-TXD)") (class "Default")
      (node (ref "U105") (pin "1") (pinfunction "TXD_1") (pintype "input"))
      (node (ref "U106") (pin "7") (pinfunction "OUTA_7") (pintype "output"))
    )
    (net (code "59") (name "Net-(X100-CC1)") (class "Default")
      (node (ref "R118") (pin "2") (pinfunction "2_2") (pintype "passive"))
      (node (ref "X100") (pin "A5") (pinfunction "CC1_A5") (pintype "passive"))
    )
    (net (code "60") (name "Net-(X100-CC2)") (class "Default")
      (node (ref "R100") (pin "2") (pinfunction "2_2") (pintype "passive"))
      (node (ref "X100") (pin "B5") (pinfunction "CC2_B5") (pintype "passive"))
    )
    (net (code "61") (name "unconnected-(U100-(XOUT0)PA15-Pad32)") (class "Default")
      (node (ref "U100") (pin "32") (pinfunction "(XOUT0)PA15_32") (pintype "bidirectional"))
    )
    (net (code "62") (name "unconnected-(U100-PA00{slash}COM1_0-Pad1)") (class "Default")
      (node (ref "U100") (pin "1") (pinfunction "PA00/COM1_0_1") (pintype "bidirectional+no_connect"))
    )
    (net (code "63") (name "unconnected-(U100-PA01{slash}COM1_1-Pad2)") (class "Default")
      (node (ref "U100") (pin "2") (pinfunction "PA01/COM1_1_2") (pintype "bidirectional+no_connect"))
    )
    (net (code "64") (name "unconnected-(U100-PA03{slash}AIN0_1{slash}VREFA-Pad4)") (class "Default")
      (node (ref "U100") (pin "4") (pinfunction "PA03/AIN0_1/VREFA_4") (pintype "bidirectional+no_connect"))
    )
    (net (code "65") (name "unconnected-(U100-PA04{slash}AIN0_4{slash}VREFB{slash}COM0_0-Pad13)") (class "Default")
      (node (ref "U100") (pin "13") (pinfunction "PA04/AIN0_4/VREFB/COM0_0_13") (pintype "bidirectional+no_connect"))
    )
    (net (code "66") (name "unconnected-(U100-PA05{slash}AIN0_5{slash}DAC1{slash}COM0_1-Pad14)") (class "Default")
      (node (ref "U100") (pin "14") (pinfunction "PA05/AIN0_5/DAC1/COM0_1_14") (pintype "bidirectional+no_connect"))
    )
    (net (code "67") (name "unconnected-(U100-PA10{slash}AIN0_10{slash}COM0_2{slash}COM2_2-Pad19)") (class "Default")
      (node (ref "U100") (pin "19") (pinfunction "PA10/AIN0_10/COM0_2/COM2_2_19") (pintype "bidirectional+no_connect"))
    )
    (net (code "68") (name "unconnected-(U100-PA11{slash}AIN0_11{slash}COM0_3{slash}COM2_3-Pad20)") (class "Default")
      (node (ref "U100") (pin "20") (pinfunction "PA11/AIN0_11/COM0_3/COM2_3_20") (pintype "bidirectional+no_connect"))
    )
    (net (code "69") (name "unconnected-(U100-PA12{slash}COM2_0{slash}COM4_1-Pad29)") (class "Default")
      (node (ref "U100") (pin "29") (pinfunction "PA12/COM2_0/COM4_1_29") (pintype "bidirectional+no_connect"))
    )
    (net (code "70") (name "unconnected-(U100-PA13{slash}COM2_1{slash}COM4_0-Pad30)") (class "Default")
      (node (ref "U100") (pin "30") (pinfunction "PA13/COM2_1/COM4_0_30") (pintype "bidirectional+no_connect"))
    )
    (net (code "71") (name "unconnected-(U100-PA16{slash}COM1_0{slash}COM3_1-Pad35)") (class "Default")
      (node (ref "U100") (pin "35") (pinfunction "PA16/COM1_0/COM3_1_35") (pintype "bidirectional+no_connect"))
    )
    (net (code "72") (name "unconnected-(U100-PA17{slash}COM1_1{slash}COM3_0-Pad36)") (class "Default")
      (node (ref "U100") (pin "36") (pinfunction "PA17/COM1_1/COM3_0_36") (pintype "bidirectional+no_connect"))
    )
    (net (code "73") (name "unconnected-(U100-PA20{slash}COM5_2{slash}COM3_2-Pad41)") (class "Default")
      (node (ref "U100") (pin "41") (pinfunction "PA20/COM5_2/COM3_2_41") (pintype "bidirectional+no_connect"))
    )
    (net (code "74") (name "unconnected-(U100-PA21{slash}COM5_3{slash}COM3_3-Pad42)") (class "Default")
      (node (ref "U100") (pin "42") (pinfunction "PA21/COM5_3/COM3_3_42") (pintype "bidirectional+no_connect"))
    )
    (net (code "75") (name "unconnected-(U100-PA27-Pad51)") (class "Default")
      (node (ref "U100") (pin "51") (pinfunction "PA27_51") (pintype "bidirectional+no_connect"))
    )
    (net (code "76") (name "unconnected-(U100-PB04{slash}AIN1_6-Pad5)") (class "Default")
      (node (ref "U100") (pin "5") (pinfunction "PB04/AIN1_6_5") (pintype "bidirectional+no_connect"))
    )
    (net (code "77") (name "unconnected-(U100-PB05{slash}AIN1_7-Pad6)") (class "Default")
      (node (ref "U100") (pin "6") (pinfunction "PB05/AIN1_7_6") (pintype "bidirectional+no_connect"))
    )
    (net (code "78") (name "unconnected-(U100-PB06{slash}AIN1_8-Pad9)") (class "Default")
      (node (ref "U100") (pin "9") (pinfunction "PB06/AIN1_8_9") (pintype "bidirectional+no_connect"))
    )
    (net (code "79") (name "unconnected-(U100-PB07{slash}AIN1_9-Pad10)") (class "Default")
      (node (ref "U100") (pin "10") (pinfunction "PB07/AIN1_9_10") (pintype "bidirectional+no_connect"))
    )
    (net (code "80") (name "unconnected-(U100-PB08{slash}AIN0_2{slash}AIN1_0{slash}COM4_0-Pad11)") (class "Default")
      (node (ref "U100") (pin "11") (pinfunction "PB08/AIN0_2/AIN1_0/COM4_0_11") (pintype "bidirectional+no_connect"))
    )
    (net (code "81") (name "unconnected-(U100-PB09{slash}AIN0_3{slash}AIN1_1{slash}COM4_1-Pad12)") (class "Default")
      (node (ref "U100") (pin "12") (pinfunction "PB09/AIN0_3/AIN1_1/COM4_1_12") (pintype "bidirectional+no_connect"))
    )
    (net (code "82") (name "unconnected-(U100-PB10{slash}COM4_2-Pad23)") (class "Default")
      (node (ref "U100") (pin "23") (pinfunction "PB10/COM4_2_23") (pintype "bidirectional+no_connect"))
    )
    (net (code "83") (name "unconnected-(U100-PB11{slash}COM4_3-Pad24)") (class "Default")
      (node (ref "U100") (pin "24") (pinfunction "PB11/COM4_3_24") (pintype "bidirectional+no_connect"))
    )
    (net (code "84") (name "unconnected-(U100-PB12{slash}COM4_0{slash}CAN1_TX-Pad25)") (class "Default")
      (node (ref "U100") (pin "25") (pinfunction "PB12/COM4_0/CAN1_TX_25") (pintype "bidirectional+no_connect"))
    )
    (net (code "85") (name "unconnected-(U100-PB13{slash}COM4_1{slash}CAN1_RX-Pad26)") (class "Default")
      (node (ref "U100") (pin "26") (pinfunction "PB13/COM4_1/CAN1_RX_26") (pintype "bidirectional+no_connect"))
    )
    (net (code "86") (name "unconnected-(U100-PB22{slash}COM5_2{slash}COM1_2{slash}XIN1-Pad49)") (class "Default")
      (node (ref "U100") (pin "49") (pinfunction "PB22/COM5_2/COM1_2/XIN1_49") (pintype "bidirectional+no_connect"))
    )
    (net (code "87") (name "unconnected-(U100-PB23{slash}COM5_3{slash}COM1_3{slash}XOUT1-Pad50)") (class "Default")
      (node (ref "U100") (pin "50") (pinfunction "PB23/COM5_3/COM1_3/XOUT1_50") (pintype "bidirectional+no_connect"))
    )
    (net (code "88") (name "unconnected-(U100-PB30{slash}SWO-Pad59)") (class "Default")
      (node (ref "U100") (pin "59") (pinfunction "PB30/SWO_59") (pintype "bidirectional+no_connect"))
    )
    (net (code "89") (name "unconnected-(U100-PB31{slash}COM5_0{slash}COM7_1-Pad60)") (class "Default")
      (node (ref "U100") (pin "60") (pinfunction "PB31/COM5_0/COM7_1_60") (pintype "bidirectional+no_connect"))
    )
    (net (code "90") (name "unconnected-(U100-VSW-Pad55)") (class "Default")
      (node (ref "U100") (pin "55") (pinfunction "VSW_55") (pintype "passive+no_connect"))
    )
    (net (code "91") (name "unconnected-(X100-SBU1-PadA8)") (class "Default")
      (node (ref "X100") (pin "A8") (pinfunction "SBU1_A8") (pintype "passive"))
    )
    (net (code "92") (name "unconnected-(X100-SBU2-PadB8)") (class "Default")
      (node (ref "X100") (pin "B8") (pinfunction "SBU2_B8") (pintype "passive"))
    )
    (net (code "93") (name "unconnected-(X102-Pad4)") (class "Default")
      (node (ref "X102") (pin "4") (pinfunction "4_4") (pintype "passive"))
    )
    (net (code "94") (name "unconnected-(X102-Pad5)") (class "Default")
      (node (ref "X102") (pin "5") (pinfunction "5_5") (pintype "passive"))
    )
    (net (code "95") (name "unconnected-(X102-Pad9)") (class "Default")
      (node (ref "X102") (pin "9") (pinfunction "9_9") (pintype "passive"))
    )
    (net (code "96") (name "unconnected-(X102-PadSH)") (class "Default")
      (node (ref "X102") (pin "SH") (pinfunction "SH_SH") (pintype "passive"))
    )
    (net (code "97") (name "unconnected-(X104-KEY-Pad7)") (class "Default")
      (node (ref "X104") (pin "7") (pinfunction "KEY_7") (pintype "passive"))
    )
    (net (code "98") (name "unconnected-(X104-NC{slash}TDI-Pad8)") (class "Default")
      (node (ref "X104") (pin "8") (pinfunction "NC/TDI_8") (pintype "passive"))
    )
    (net (code "99") (name "unconnected-(X104-SWO{slash}TDO-Pad6)") (class "Default")
      (node (ref "X104") (pin "6") (pinfunction "SWO/TDO_6") (pintype "passive"))
    )
  )
)
